# 06_BUTTONS.net
KiCad netlist of a schematic drawn in Altium Designer
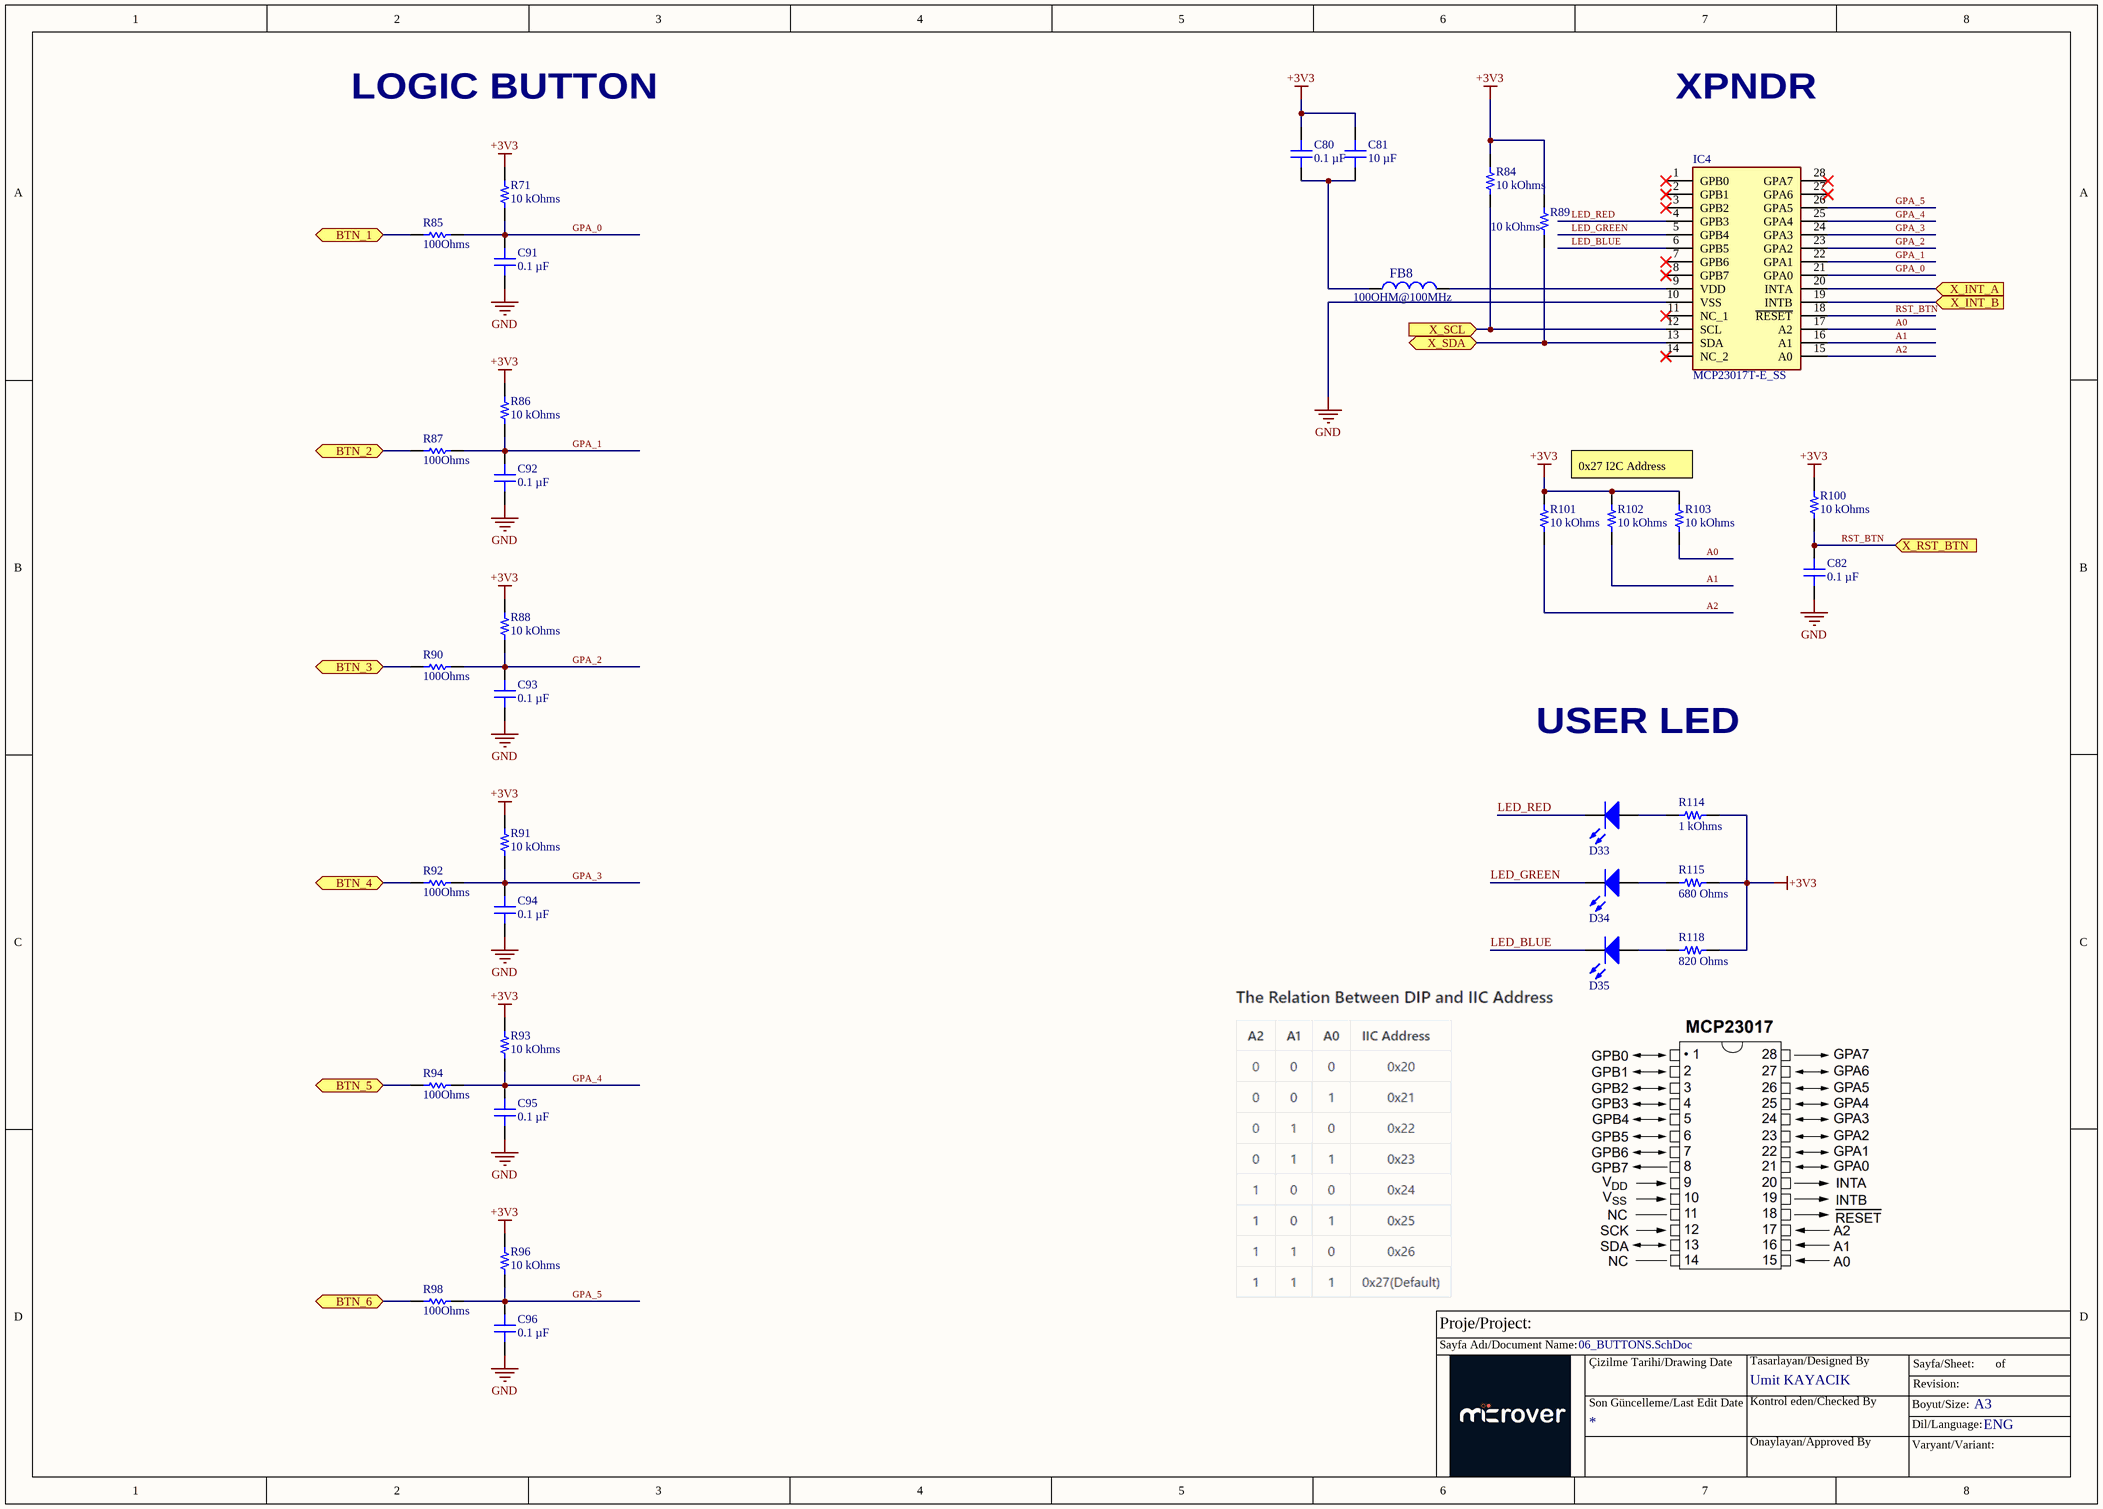
[diagram p0: 06_BUTTONS.SchDoc]

(export (version "E")
  (design (tool "Eeschema 10.0.6"))
  (components
    (comp (ref "C80")
      (value "0.1 µF")
      (footprint "CAP 0603_1608")
      (description "CAP CER 0.1UF 50V X7R 0603")
      (fields
        (field (name "PART NUMBER") "VJ0603Y104KXAPW1BC")
        (field (name "MANUFACTURER") "Vishay Vitramon")
      )
      (libsource (lib "Celestial Altium Library - altium_library") (part "Capacitor"))
    )
    (comp (ref "C81")
      (value "10 µF")
      (footprint "CAP 0603_1608")
      (description "CAP CER 10UF 16V X5R 0603")
      (fields (field (name "PART NUMBER") "KGM15CR51C106KT") (field (name "MANUFACTURER") "KYOCERA AVX"))
      (libsource (lib "Celestial Altium Library - altium_library") (part "Capacitor"))
    )
    (comp (ref "C82")
      (value "0.1 µF")
      (footprint "CAP 0603_1608")
      (description "CAP CER 0.1UF 50V X7R 0603")
      (fields
        (field (name "PART NUMBER") "VJ0603Y104KXAPW1BC")
        (field (name "MANUFACTURER") "Vishay Vitramon")
      )
      (libsource (lib "Celestial Altium Library - altium_library") (part "Capacitor"))
    )
    (comp (ref "C91")
      (value "0.1 µF")
      (footprint "CAP0603")
      (description "CAP CER 0.1UF 50V X7R 0603")
      (fields
        (field (name "PART NUMBER") "VJ0603Y104KXAPW1BC")
        (field (name "MANUFACTURER") "Vishay Vitramon")
      )
      (libsource (lib "Celestial Altium Library - altium_library") (part "Capacitor"))
    )
    (comp (ref "C92")
      (value "0.1 µF")
      (footprint "CAP0603")
      (description "CAP CER 0.1UF 50V X7R 0603")
      (fields
        (field (name "PART NUMBER") "VJ0603Y104KXAPW1BC")
        (field (name "MANUFACTURER") "Vishay Vitramon")
      )
      (libsource (lib "Celestial Altium Library - altium_library") (part "Capacitor"))
    )
    (comp (ref "C93")
      (value "0.1 µF")
      (footprint "CAP0603")
      (description "CAP CER 0.1UF 50V X7R 0603")
      (fields
        (field (name "PART NUMBER") "VJ0603Y104KXAPW1BC")
        (field (name "MANUFACTURER") "Vishay Vitramon")
      )
      (libsource (lib "Celestial Altium Library - altium_library") (part "Capacitor"))
    )
    (comp (ref "C94")
      (value "0.1 µF")
      (footprint "CAP0603")
      (description "CAP CER 0.1UF 50V X7R 0603")
      (fields
        (field (name "PART NUMBER") "VJ0603Y104KXAPW1BC")
        (field (name "MANUFACTURER") "Vishay Vitramon")
      )
      (libsource (lib "Celestial Altium Library - altium_library") (part "Capacitor"))
    )
    (comp (ref "C95")
      (value "0.1 µF")
      (footprint "CAP0603")
      (description "CAP CER 0.1UF 50V X7R 0603")
      (fields
        (field (name "PART NUMBER") "VJ0603Y104KXAPW1BC")
        (field (name "MANUFACTURER") "Vishay Vitramon")
      )
      (libsource (lib "Celestial Altium Library - altium_library") (part "Capacitor"))
    )
    (comp (ref "C96")
      (value "0.1 µF")
      (footprint "CAP0603")
      (description "CAP CER 0.1UF 50V X7R 0603")
      (fields
        (field (name "PART NUMBER") "VJ0603Y104KXAPW1BC")
        (field (name "MANUFACTURER") "Vishay Vitramon")
      )
      (libsource (lib "Celestial Altium Library - altium_library") (part "Capacitor"))
    )
    (comp (ref "D33")
      (value "LED RED")
      (footprint "LED0805")
      (description "SMD mono-color Chip LED, WL-SMCW, Red")
      (fields
        (field (name "MANUFACTURER PART NUMBER") "150080RS75000")
        (field (name "MANUFACTURER") "Wuerth Elektronik")
      )
      (libsource (lib "HW_HOLLAND_NCDM_MONITOR_R1") (part "LED0805_RED"))
    )
    (comp (ref "D34")
      (value "LED GREEN")
      (footprint "LED0805")
      (description "Green 570nm LED Indication - Discrete 2.1V 0805 (2012 Metric)")
      (fields
        (field (name "MANUFACTURER PART NUMBER") "CMD17-21VGC/TR8")
        (field (name "MANUFACTURER") "Visual Communications Company - VCC")
      )
      (libsource (lib "HW_HOLLAND_NCDM_MONITOR_R1") (part "LED0805_GREEN"))
    )
    (comp (ref "D35")
      (value "LED BLUE")
      (footprint "LED0805")
      (description "Blue 470nm LED Indication - Discrete 3V 0805 (2012 Metric)")
      (fields (field (name "MANUFACTURER PART NUMBER") "IN-S85AT5B") (field (name "MANUFACTURER") "Inolux"))
      (libsource (lib "HW_HOLLAND_NCDM_MONITOR_R1") (part "LED0805_BLUE"))
    )
    (comp (ref "FB8")
      (value "100OHM@100MHz")
      (footprint "FB 0603(1608)")
      (description "100 Ohms @ 100 MHz 1 Power Line Ferrite Bead 0603 (1608 Metric) 2A 40mOhm")
      (fields
        (field (name "MANUFACTURER") "TDK")
        (field (name "MANUFACTURER PART NUMBER") "MPZ1608Y101BTA00")
      )
      (libsource (lib "HW_HOLLAND_NCDM_MONITOR_R1") (part "FB0603_100OHM_100MHz"))
    )
    (comp (ref "IC4")
      (value "MCP23017T-E_SS")
      (footprint "SOP65P780X200-28N")
      (description "Integrated Circuit")
      (fields
        (field (name "MANUFACTURER_PART_NUMBER") "MCP23017T-E/SS")
        (field (name "MOUSER PART NUMBER") "579-MCP23017T-E/SS")
      )
      (libsource (lib "HW_HOLLAND_NCDM_MONITOR_R1") (part "MCP23017T-E_SS"))
    )
    (comp (ref "R71")
      (value "10 kOhms")
      (footprint "RES0402(1005)")
      (description "RES 10K OHM 0.1% 1/10W 0402")
      (fields
        (field (name "PART NUMBER") "RP73PF1E10KBTD")
        (field (name "MANUFACTURER") "TE Connectivity Passive Product")
      )
      (libsource (lib "Celestial Altium Library - altium_library") (part "Resistor"))
    )
    (comp (ref "R84")
      (value "10 kOhms")
      (footprint "RES 0402_1005")
      (description "RES 10K OHM 0.1% 1/10W 0402")
      (fields
        (field (name "PART NUMBER") "RP73PF1E10KBTD")
        (field (name "MANUFACTURER") "TE Connectivity Passive Product")
      )
      (libsource (lib "Celestial Altium Library - altium_library") (part "Resistor"))
    )
    (comp (ref "R85")
      (value "100Ohms")
      (footprint "RESC1005X40X25ML05T10")
      (fields (field (name "PART NUMBER") "RC0402FR-07100RL") (field (name "MANUFACTURER") "Yageo / Phycomp"))
      (libsource (lib "Altium Content Vault") (part "RES"))
    )
    (comp (ref "R86")
      (value "10 kOhms")
      (footprint "RES0402(1005)")
      (description "RES 10K OHM 0.1% 1/10W 0402")
      (fields
        (field (name "PART NUMBER") "RP73PF1E10KBTD")
        (field (name "MANUFACTURER") "TE Connectivity Passive Product")
      )
      (libsource (lib "Celestial Altium Library - altium_library") (part "Resistor"))
    )
    (comp (ref "R87")
      (value "100Ohms")
      (footprint "RESC1005X40X25ML05T10")
      (fields (field (name "PART NUMBER") "RC0402FR-07100RL") (field (name "MANUFACTURER") "Yageo / Phycomp"))
      (libsource (lib "Altium Content Vault") (part "RES"))
    )
    (comp (ref "R88")
      (value "10 kOhms")
      (footprint "RES0402(1005)")
      (description "RES 10K OHM 0.1% 1/10W 0402")
      (fields
        (field (name "PART NUMBER") "RP73PF1E10KBTD")
        (field (name "MANUFACTURER") "TE Connectivity Passive Product")
      )
      (libsource (lib "Celestial Altium Library - altium_library") (part "Resistor"))
    )
    (comp (ref "R89")
      (value "10 kOhms")
      (footprint "RES 0402_1005")
      (description "RES 10K OHM 0.1% 1/10W 0402")
      (fields
        (field (name "PART NUMBER") "RP73PF1E10KBTD")
        (field (name "MANUFACTURER") "TE Connectivity Passive Product")
      )
      (libsource (lib "Celestial Altium Library - altium_library") (part "Resistor"))
    )
    (comp (ref "R90")
      (value "100Ohms")
      (footprint "RESC1005X40X25ML05T10")
      (fields (field (name "PART NUMBER") "RC0402FR-07100RL") (field (name "MANUFACTURER") "Yageo / Phycomp"))
      (libsource (lib "Altium Content Vault") (part "RES"))
    )
    (comp (ref "R91")
      (value "10 kOhms")
      (footprint "RES0402(1005)")
      (description "RES 10K OHM 0.1% 1/10W 0402")
      (fields
        (field (name "PART NUMBER") "RP73PF1E10KBTD")
        (field (name "MANUFACTURER") "TE Connectivity Passive Product")
      )
      (libsource (lib "Celestial Altium Library - altium_library") (part "Resistor"))
    )
    (comp (ref "R92")
      (value "100Ohms")
      (footprint "RESC1005X40X25ML05T10")
      (fields (field (name "PART NUMBER") "RC0402FR-07100RL") (field (name "MANUFACTURER") "Yageo / Phycomp"))
      (libsource (lib "Altium Content Vault") (part "RES"))
    )
    (comp (ref "R93")
      (value "10 kOhms")
      (footprint "RES0402(1005)")
      (description "RES 10K OHM 0.1% 1/10W 0402")
      (fields
        (field (name "PART NUMBER") "RP73PF1E10KBTD")
        (field (name "MANUFACTURER") "TE Connectivity Passive Product")
      )
      (libsource (lib "Celestial Altium Library - altium_library") (part "Resistor"))
    )
    (comp (ref "R94")
      (value "100Ohms")
      (footprint "RESC1005X40X25ML05T10")
      (fields (field (name "PART NUMBER") "RC0402FR-07100RL") (field (name "MANUFACTURER") "Yageo / Phycomp"))
      (libsource (lib "Altium Content Vault") (part "RES"))
    )
    (comp (ref "R96")
      (value "10 kOhms")
      (footprint "RES0402(1005)")
      (description "RES 10K OHM 0.1% 1/10W 0402")
      (fields
        (field (name "PART NUMBER") "RP73PF1E10KBTD")
        (field (name "MANUFACTURER") "TE Connectivity Passive Product")
      )
      (libsource (lib "Celestial Altium Library - altium_library") (part "Resistor"))
    )
    (comp (ref "R98")
      (value "100Ohms")
      (footprint "RESC1005X40X25ML05T10")
      (fields (field (name "PART NUMBER") "RC0402FR-07100RL") (field (name "MANUFACTURER") "Yageo / Phycomp"))
      (libsource (lib "Altium Content Vault") (part "RES"))
    )
    (comp (ref "R100")
      (value "10 kOhms")
      (footprint "RES 0402_1005")
      (description "RES 10K OHM 0.1% 1/10W 0402")
      (fields
        (field (name "PART NUMBER") "RP73PF1E10KBTD")
        (field (name "MANUFACTURER") "TE Connectivity Passive Product")
      )
      (libsource (lib "Celestial Altium Library - altium_library") (part "Resistor"))
    )
    (comp (ref "R101")
      (value "10 kOhms")
      (footprint "RES 0402_1005")
      (description "RES 10K OHM 0.1% 1/10W 0402")
      (fields
        (field (name "PART NUMBER") "RP73PF1E10KBTD")
        (field (name "MANUFACTURER") "TE Connectivity Passive Product")
      )
      (libsource (lib "Celestial Altium Library - altium_library") (part "Resistor"))
    )
    (comp (ref "R102")
      (value "10 kOhms")
      (footprint "RES 0402_1005")
      (description "RES 10K OHM 0.1% 1/10W 0402")
      (fields
        (field (name "PART NUMBER") "RP73PF1E10KBTD")
        (field (name "MANUFACTURER") "TE Connectivity Passive Product")
      )
      (libsource (lib "Celestial Altium Library - altium_library") (part "Resistor"))
    )
    (comp (ref "R103")
      (value "10 kOhms")
      (footprint "RES 0402_1005")
      (description "RES 10K OHM 0.1% 1/10W 0402")
      (fields
        (field (name "PART NUMBER") "RP73PF1E10KBTD")
        (field (name "MANUFACTURER") "TE Connectivity Passive Product")
      )
      (libsource (lib "Celestial Altium Library - altium_library") (part "Resistor"))
    )
    (comp (ref "R114")
      (value "1 kOhms")
      (footprint "RES 0402_1005")
      (description "0402 ANTI-SULFUR RES. , 0.5%, 1K")
      (fields
        (field (name "PART NUMBER") "ERJ-U02D1001X")
        (field (name "MANUFACTURER") "Panasonic Electronic Components")
      )
      (libsource (lib "Celestial Altium Library - altium_library") (part "Resistor"))
    )
    (comp (ref "R115")
      (value "680 Ohms")
      (footprint "RES 0402_1005")
      (description "RES 680 OHM 1% 1/10W 0402 SMD")
      (fields
        (field (name "PART NUMBER") "ERJ-U02F6800X")
        (field (name "MANUFACTURER") "Panasonic Electronic Components")
      )
      (libsource (lib "Celestial Altium Library - altium_library") (part "Resistor"))
    )
    (comp (ref "R118")
      (value "820 Ohms")
      (footprint "RES 0402_1005")
      (description "RES SMD 820 OHM 1% 1/10W 0402")
      (fields
        (field (name "PART NUMBER") "ERJ-2RKF8200X")
        (field (name "MANUFACTURER") "Panasonic Electronic Components")
      )
      (libsource (lib "Celestial Altium Library - altium_library") (part "Resistor"))
    )
  )
  (nets
    (net (code "1") (name "+3V3") (class "Default")
      (node (ref "C80") (pin "2") (pinfunction "2_2") (pintype "passive"))
      (node (ref "C81") (pin "2") (pinfunction "2_2") (pintype "passive"))
      (node (ref "R100") (pin "2") (pinfunction "2_2") (pintype "passive"))
      (node (ref "R101") (pin "2") (pinfunction "2_2") (pintype "passive"))
      (node (ref "R102") (pin "2") (pinfunction "2_2") (pintype "passive"))
      (node (ref "R103") (pin "2") (pinfunction "2_2") (pintype "passive"))
      (node (ref "R114") (pin "2") (pinfunction "2_2") (pintype "passive"))
      (node (ref "R115") (pin "2") (pinfunction "2_2") (pintype "passive"))
      (node (ref "R118") (pin "2") (pinfunction "2_2") (pintype "passive"))
      (node (ref "R71") (pin "2") (pinfunction "2_2") (pintype "passive"))
      (node (ref "R84") (pin "2") (pinfunction "2_2") (pintype "passive"))
      (node (ref "R86") (pin "2") (pinfunction "2_2") (pintype "passive"))
      (node (ref "R88") (pin "2") (pinfunction "2_2") (pintype "passive"))
      (node (ref "R89") (pin "2") (pinfunction "2_2") (pintype "passive"))
      (node (ref "R91") (pin "2") (pinfunction "2_2") (pintype "passive"))
      (node (ref "R93") (pin "2") (pinfunction "2_2") (pintype "passive"))
      (node (ref "R96") (pin "2") (pinfunction "2_2") (pintype "passive"))
    )
    (net (code "2") (name "/A0") (class "Default")
      (node (ref "IC4") (pin "17") (pinfunction "A2_17") (pintype "passive"))
      (node (ref "R103") (pin "1") (pinfunction "1_1") (pintype "passive"))
    )
    (net (code "3") (name "/A1") (class "Default")
      (node (ref "IC4") (pin "16") (pinfunction "A1_16") (pintype "passive"))
      (node (ref "R102") (pin "1") (pinfunction "1_1") (pintype "passive"))
    )
    (net (code "4") (name "/A2") (class "Default")
      (node (ref "IC4") (pin "15") (pinfunction "A0_15") (pintype "passive"))
      (node (ref "R101") (pin "1") (pinfunction "1_1") (pintype "passive"))
    )
    (net (code "5") (name "/BTN_1") (class "Default")
      (node (ref "R85") (pin "1") (pinfunction "1_1") (pintype "passive"))
    )
    (net (code "6") (name "/BTN_2") (class "Default")
      (node (ref "R87") (pin "1") (pinfunction "1_1") (pintype "passive"))
    )
    (net (code "7") (name "/BTN_3") (class "Default")
      (node (ref "R90") (pin "1") (pinfunction "1_1") (pintype "passive"))
    )
    (net (code "8") (name "/BTN_4") (class "Default")
      (node (ref "R92") (pin "1") (pinfunction "1_1") (pintype "passive"))
    )
    (net (code "9") (name "/BTN_5") (class "Default")
      (node (ref "R94") (pin "1") (pinfunction "1_1") (pintype "passive"))
    )
    (net (code "10") (name "/BTN_6") (class "Default")
      (node (ref "R98") (pin "1") (pinfunction "1_1") (pintype "passive"))
    )
    (net (code "11") (name "/GPA_0") (class "Default")
      (node (ref "C91") (pin "2") (pinfunction "2_2") (pintype "passive"))
      (node (ref "IC4") (pin "21") (pinfunction "GPA0_21") (pintype "passive"))
      (node (ref "R71") (pin "1") (pinfunction "1_1") (pintype "passive"))
      (node (ref "R85") (pin "2") (pinfunction "2_2") (pintype "passive"))
    )
    (net (code "12") (name "/GPA_1") (class "Default")
      (node (ref "C92") (pin "2") (pinfunction "2_2") (pintype "passive"))
      (node (ref "IC4") (pin "22") (pinfunction "GPA1_22") (pintype "passive"))
      (node (ref "R86") (pin "1") (pinfunction "1_1") (pintype "passive"))
      (node (ref "R87") (pin "2") (pinfunction "2_2") (pintype "passive"))
    )
    (net (code "13") (name "/GPA_2") (class "Default")
      (node (ref "C93") (pin "2") (pinfunction "2_2") (pintype "passive"))
      (node (ref "IC4") (pin "23") (pinfunction "GPA2_23") (pintype "passive"))
      (node (ref "R88") (pin "1") (pinfunction "1_1") (pintype "passive"))
      (node (ref "R90") (pin "2") (pinfunction "2_2") (pintype "passive"))
    )
    (net (code "14") (name "/GPA_3") (class "Default")
      (node (ref "C94") (pin "2") (pinfunction "2_2") (pintype "passive"))
      (node (ref "IC4") (pin "24") (pinfunction "GPA3_24") (pintype "passive"))
      (node (ref "R91") (pin "1") (pinfunction "1_1") (pintype "passive"))
      (node (ref "R92") (pin "2") (pinfunction "2_2") (pintype "passive"))
    )
    (net (code "15") (name "/GPA_4") (class "Default")
      (node (ref "C95") (pin "2") (pinfunction "2_2") (pintype "passive"))
      (node (ref "IC4") (pin "25") (pinfunction "GPA4_25") (pintype "passive"))
      (node (ref "R93") (pin "1") (pinfunction "1_1") (pintype "passive"))
      (node (ref "R94") (pin "2") (pinfunction "2_2") (pintype "passive"))
    )
    (net (code "16") (name "/GPA_5") (class "Default")
      (node (ref "C96") (pin "2") (pinfunction "2_2") (pintype "passive"))
      (node (ref "IC4") (pin "26") (pinfunction "GPA5_26") (pintype "passive"))
      (node (ref "R96") (pin "1") (pinfunction "1_1") (pintype "passive"))
      (node (ref "R98") (pin "2") (pinfunction "2_2") (pintype "passive"))
    )
    (net (code "17") (name "/LED_BLUE") (class "Default")
      (node (ref "D35") (pin "1") (pinfunction "K_1") (pintype "passive"))
      (node (ref "IC4") (pin "6") (pinfunction "GPB5_6") (pintype "passive"))
    )
    (net (code "18") (name "/LED_GREEN") (class "Default")
      (node (ref "D34") (pin "1") (pinfunction "K_1") (pintype "passive"))
      (node (ref "IC4") (pin "5") (pinfunction "GPB4_5") (pintype "passive"))
    )
    (net (code "19") (name "/LED_RED") (class "Default")
      (node (ref "D33") (pin "1") (pinfunction "K_1") (pintype "passive"))
      (node (ref "IC4") (pin "4") (pinfunction "GPB3_4") (pintype "passive"))
    )
    (net (code "20") (name "/RST_BTN") (class "Default")
      (node (ref "C82") (pin "2") (pinfunction "2_2") (pintype "passive"))
      (node (ref "IC4") (pin "18") (pinfunction "~{RESET}_18") (pintype "passive"))
      (node (ref "R100") (pin "1") (pinfunction "1_1") (pintype "passive"))
    )
    (net (code "21") (name "/X_INT_A") (class "Default")
      (node (ref "IC4") (pin "20") (pinfunction "INTA_20") (pintype "passive"))
    )
    (net (code "22") (name "/X_INT_B") (class "Default")
      (node (ref "IC4") (pin "19") (pinfunction "INTB_19") (pintype "passive"))
    )
    (net (code "23") (name "/X_SCL") (class "Default")
      (node (ref "IC4") (pin "12") (pinfunction "SCL_12") (pintype "passive"))
      (node (ref "R84") (pin "1") (pinfunction "1_1") (pintype "passive"))
    )
    (net (code "24") (name "/X_SDA") (class "Default")
      (node (ref "IC4") (pin "13") (pinfunction "SDA_13") (pintype "passive"))
      (node (ref "R89") (pin "1") (pinfunction "1_1") (pintype "passive"))
    )
    (net (code "25") (name "GND") (class "Default")
      (node (ref "C82") (pin "1") (pinfunction "1_1") (pintype "passive"))
      (node (ref "C91") (pin "1") (pinfunction "1_1") (pintype "passive"))
      (node (ref "C92") (pin "1") (pinfunction "1_1") (pintype "passive"))
      (node (ref "C93") (pin "1") (pinfunction "1_1") (pintype "passive"))
      (node (ref "C94") (pin "1") (pinfunction "1_1") (pintype "passive"))
      (node (ref "C95") (pin "1") (pinfunction "1_1") (pintype "passive"))
      (node (ref "C96") (pin "1") (pinfunction "1_1") (pintype "passive"))
      (node (ref "IC4") (pin "10") (pinfunction "VSS_10") (pintype "passive"))
    )
    (net (code "26") (name "Net-(C80-Pad1)") (class "Default")
      (node (ref "C80") (pin "1") (pinfunction "1_1") (pintype "passive"))
      (node (ref "C81") (pin "1") (pinfunction "1_1") (pintype "passive"))
      (node (ref "FB8") (pin "2") (pinfunction "2_2") (pintype "passive"))
    )
    (net (code "27") (name "Net-(D33-A)") (class "Default")
      (node (ref "D33") (pin "2") (pinfunction "A_2") (pintype "passive"))
      (node (ref "R114") (pin "1") (pinfunction "1_1") (pintype "passive"))
    )
    (net (code "28") (name "Net-(D34-A)") (class "Default")
      (node (ref "D34") (pin "2") (pinfunction "A_2") (pintype "passive"))
      (node (ref "R115") (pin "1") (pinfunction "1_1") (pintype "passive"))
    )
    (net (code "29") (name "Net-(D35-A)") (class "Default")
      (node (ref "D35") (pin "2") (pinfunction "A_2") (pintype "passive"))
      (node (ref "R118") (pin "1") (pinfunction "1_1") (pintype "passive"))
    )
    (net (code "30") (name "Net-(IC4-VDD)") (class "Default")
      (node (ref "FB8") (pin "1") (pinfunction "1_1") (pintype "passive"))
      (node (ref "IC4") (pin "9") (pinfunction "VDD_9") (pintype "passive"))
    )
    (net (code "31") (name "unconnected-(IC4-GPA6-Pad27)") (class "Default")
      (node (ref "IC4") (pin "27") (pinfunction "GPA6_27") (pintype "passive+no_connect"))
    )
    (net (code "32") (name "unconnected-(IC4-GPA7-Pad28)") (class "Default")
      (node (ref "IC4") (pin "28") (pinfunction "GPA7_28") (pintype "passive+no_connect"))
    )
    (net (code "33") (name "unconnected-(IC4-GPB0-Pad1)") (class "Default")
      (node (ref "IC4") (pin "1") (pinfunction "GPB0_1") (pintype "passive+no_connect"))
    )
    (net (code "34") (name "unconnected-(IC4-GPB1-Pad2)") (class "Default")
      (node (ref "IC4") (pin "2") (pinfunction "GPB1_2") (pintype "passive+no_connect"))
    )
    (net (code "35") (name "unconnected-(IC4-GPB2-Pad3)") (class "Default")
      (node (ref "IC4") (pin "3") (pinfunction "GPB2_3") (pintype "passive+no_connect"))
    )
    (net (code "36") (name "unconnected-(IC4-GPB6-Pad7)") (class "Default")
      (node (ref "IC4") (pin "7") (pinfunction "GPB6_7") (pintype "passive+no_connect"))
    )
    (net (code "37") (name "unconnected-(IC4-GPB7-Pad8)") (class "Default")
      (node (ref "IC4") (pin "8") (pinfunction "GPB7_8") (pintype "passive+no_connect"))
    )
    (net (code "38") (name "unconnected-(IC4-NC_1-Pad11)") (class "Default")
      (node (ref "IC4") (pin "11") (pinfunction "NC_1_11") (pintype "passive+no_connect"))
    )
    (net (code "39") (name "unconnected-(IC4-NC_2-Pad14)") (class "Default")
      (node (ref "IC4") (pin "14") (pinfunction "NC_2_14") (pintype "passive+no_connect"))
    )
  )
)
